# Comms.net
KiCad netlist of a schematic drawn in Altium Designer
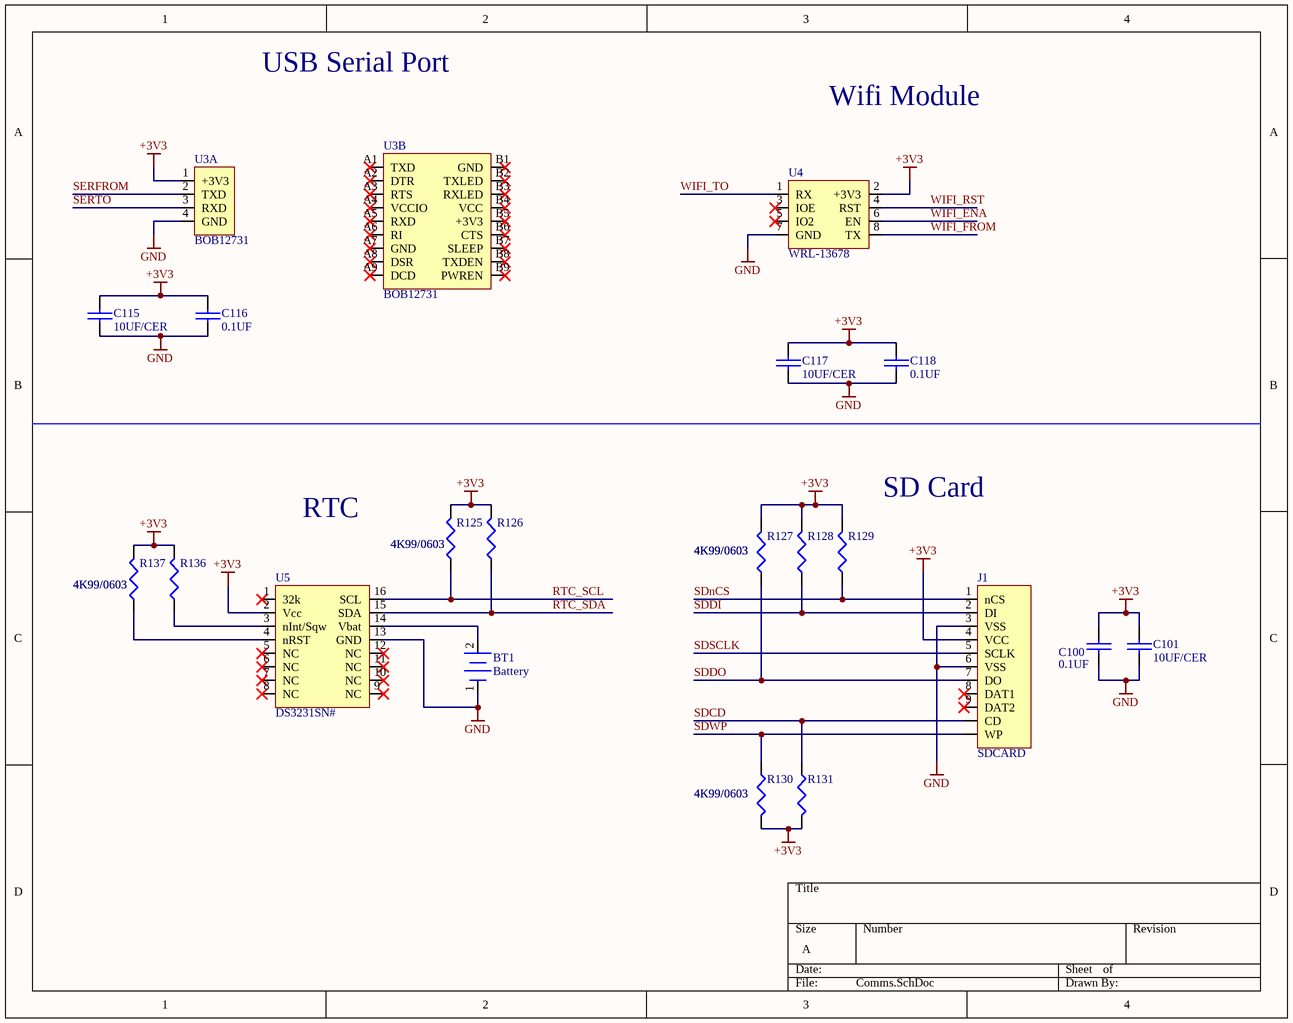
[diagram p0: Comms.SchDoc]

(export (version "E")
  (design (tool "Eeschema 10.0.6"))
  (components
    (comp (ref "BT1")
      (value "Battery")
      (footprint "BC501SM")
      (description "Battery Holder (Open) Coin, 12.0mm 1 Cell SMD (SMT) Tab")
      (fields (field (name "MFG") "MPD"))
      (libsource (lib "C64Interface") (part "BC501SM-TR"))
    )
    (comp (ref "C100")
      (value "0.1UF")
      (footprint "0603")
      (description "CAP .10UF 16V CERAMIC X7R 0603")
      (libsource (lib "*") (part "0.1UF"))
    )
    (comp (ref "C101")
      (value "10UF/CER")
      (footprint "0805")
      (description "10µF ±10% 25V Ceramic Capacitor X7S 0805")
      (libsource (lib "*") (part "10UF/CER"))
    )
    (comp (ref "C115")
      (value "10UF/CER")
      (footprint "0805")
      (description "10µF ±10% 25V Ceramic Capacitor X7S 0805")
      (libsource (lib "C64Interface") (part "10UF/CER"))
    )
    (comp (ref "C116")
      (value "0.1UF")
      (footprint "0603")
      (description "CAP .10UF 16V CERAMIC X7R 0603")
      (fields (field (name "MFG") "Kemet"))
      (libsource (lib "C64Interface") (part "0.1UF"))
    )
    (comp (ref "C117")
      (value "10UF/CER")
      (footprint "0805")
      (description "10µF ±10% 25V Ceramic Capacitor X7S 0805")
      (libsource (lib "C64Interface") (part "10UF/CER"))
    )
    (comp (ref "C118")
      (value "0.1UF")
      (footprint "0603")
      (description "CAP .10UF 16V CERAMIC X7R 0603")
      (fields (field (name "MFG") "Kemet"))
      (libsource (lib "C64Interface") (part "0.1UF"))
    )
    (comp (ref "J1")
      (value "SDCARD")
      (footprint "SDCARD2041021")
      (description "11 (9 + 2) Position Card Connector Secure Digital - SD Surface Mount, Right Angle Gold")
      (fields (field (name "MFG") "TE"))
      (libsource (lib "C64Interface") (part "SDCARD"))
    )
    (comp (ref "R125")
      (value "4K99/0603")
      (footprint "0603")
      (description "RES 4.99K OHM 1/10W 1% 0603 SMD")
      (fields (field (name "MFG") "Dale/Vishay"))
      (libsource (lib "C64Interface") (part "4K99/0603"))
    )
    (comp (ref "R126")
      (value "4K99/0603")
      (footprint "0603")
      (description "RES 4.99K OHM 1/10W 1% 0603 SMD")
      (fields (field (name "MFG") "Dale/Vishay"))
      (libsource (lib "C64Interface") (part "4K99/0603"))
    )
    (comp (ref "R127")
      (value "4K99/0603")
      (footprint "0603")
      (description "RES 4.99K OHM 1/10W 1% 0603 SMD")
      (fields (field (name "MFG") "Dale/Vishay"))
      (libsource (lib "C64Interface") (part "4K99/0603"))
    )
    (comp (ref "R128")
      (value "4K99/0603")
      (footprint "0603")
      (description "RES 4.99K OHM 1/10W 1% 0603 SMD")
      (fields (field (name "MFG") "Dale/Vishay"))
      (libsource (lib "C64Interface") (part "4K99/0603"))
    )
    (comp (ref "R129")
      (value "4K99/0603")
      (footprint "0603")
      (description "RES 4.99K OHM 1/10W 1% 0603 SMD")
      (fields (field (name "MFG") "Dale/Vishay"))
      (libsource (lib "C64Interface") (part "4K99/0603"))
    )
    (comp (ref "R130")
      (value "4K99/0603")
      (footprint "0603")
      (description "RES 4.99K OHM 1/10W 1% 0603 SMD")
      (fields (field (name "MFG") "Dale/Vishay"))
      (libsource (lib "C64Interface") (part "4K99/0603"))
    )
    (comp (ref "R131")
      (value "4K99/0603")
      (footprint "0603")
      (description "RES 4.99K OHM 1/10W 1% 0603 SMD")
      (fields (field (name "MFG") "Dale/Vishay"))
      (libsource (lib "C64Interface") (part "4K99/0603"))
    )
    (comp (ref "R136")
      (value "4K99/0603")
      (footprint "0603")
      (description "RES 4.99K OHM 1/10W 1% 0603 SMD")
      (fields (field (name "MFG") "Dale/Vishay"))
      (libsource (lib "C64Interface") (part "4K99/0603"))
    )
    (comp (ref "R137")
      (value "4K99/0603")
      (footprint "0603")
      (description "RES 4.99K OHM 1/10W 1% 0603 SMD")
      (fields (field (name "MFG") "Dale/Vishay"))
      (libsource (lib "C64Interface") (part "4K99/0603"))
    )
    (comp (ref "U3")
      (value "BOB12731")
      (footprint "BOB12731")
      (description "FT232R USB 2.0 to UART Interface Evaluation Board")
      (fields (field (name "MFG") "SparkFun"))
      (libsource (lib "C64Interface") (part "BOB12731"))
    )
    (comp (ref "U4")
      (value "WRL-13678")
      (footprint "WRL13678")
      (description "WiFi 802.11b/g/n Transceiver Module 2.4GHz ~ 2.48GHz Integrated, Trace Through Hole")
      (fields (field (name "MFG") "SparkFun"))
      (libsource (lib "C64Interface") (part "WRL-13678"))
    )
    (comp (ref "U5")
      (value "DS3231SN#")
      (footprint "SOL16")
      (description "Real Time Clock (RTC) IC Clock/Calendar I²C, 2-Wire Serial 16-SOIC (0.295\", 7.50mm Width)")
      (fields (field (name "MFG") "Maxim"))
      (libsource (lib "C64Interface") (part "DS3231SN#"))
    )
  )
  (nets
    (net (code "1") (name "+3V3") (class "Default")
      (node (ref "C100") (pin "1") (pintype "passive"))
      (node (ref "C101") (pin "2") (pintype "passive"))
      (node (ref "C115") (pin "2") (pintype "passive"))
      (node (ref "C116") (pin "1") (pintype "passive"))
      (node (ref "C117") (pin "2") (pintype "passive"))
      (node (ref "C118") (pin "1") (pintype "passive"))
      (node (ref "J1") (pin "4") (pinfunction "VCC_4") (pintype "passive"))
      (node (ref "R125") (pin "2") (pintype "passive"))
      (node (ref "R126") (pin "2") (pintype "passive"))
      (node (ref "R127") (pin "2") (pintype "passive"))
      (node (ref "R128") (pin "2") (pintype "passive"))
      (node (ref "R129") (pin "2") (pintype "passive"))
      (node (ref "R130") (pin "2") (pintype "passive"))
      (node (ref "R131") (pin "2") (pintype "passive"))
      (node (ref "R136") (pin "2") (pintype "passive"))
      (node (ref "R137") (pin "2") (pintype "passive"))
      (node (ref "U3") (pin "1") (pinfunction "+3V3_1") (pintype "passive"))
      (node (ref "U4") (pin "2") (pinfunction "+3V3_2") (pintype "passive"))
      (node (ref "U5") (pin "2") (pinfunction "Vcc_2") (pintype "passive"))
    )
    (net (code "2") (name "/RTC_SCL") (class "Default")
      (node (ref "R125") (pin "1") (pintype "passive"))
      (node (ref "U5") (pin "16") (pinfunction "SCL_16") (pintype "passive"))
    )
    (net (code "3") (name "/RTC_SDA") (class "Default")
      (node (ref "R126") (pin "1") (pintype "passive"))
      (node (ref "U5") (pin "15") (pinfunction "SDA_15") (pintype "passive"))
    )
    (net (code "4") (name "/SDCD") (class "Default")
      (node (ref "J1") (pin "CD") (pinfunction "CD_CD") (pintype "passive"))
      (node (ref "R131") (pin "1") (pintype "passive"))
    )
    (net (code "5") (name "/SDDI") (class "Default")
      (node (ref "J1") (pin "2") (pinfunction "DI_2") (pintype "passive"))
      (node (ref "R128") (pin "1") (pintype "passive"))
    )
    (net (code "6") (name "/SDDO") (class "Default")
      (node (ref "J1") (pin "7") (pinfunction "DO_7") (pintype "passive"))
      (node (ref "R127") (pin "1") (pintype "passive"))
    )
    (net (code "7") (name "/SDSCLK") (class "Default")
      (node (ref "J1") (pin "5") (pinfunction "SCLK_5") (pintype "passive"))
    )
    (net (code "8") (name "/SDWP") (class "Default")
      (node (ref "J1") (pin "WP") (pinfunction "WP_WP") (pintype "passive"))
      (node (ref "R130") (pin "1") (pintype "passive"))
    )
    (net (code "9") (name "/SDnCS") (class "Default")
      (node (ref "J1") (pin "1") (pinfunction "nCS_1") (pintype "passive"))
      (node (ref "R129") (pin "1") (pintype "passive"))
    )
    (net (code "10") (name "/SERFROM") (class "Default")
      (node (ref "U3") (pin "2") (pinfunction "TXD_2") (pintype "passive"))
    )
    (net (code "11") (name "/SERTO") (class "Default")
      (node (ref "U3") (pin "3") (pinfunction "RXD_3") (pintype "passive"))
    )
    (net (code "12") (name "/WIFI_ENA") (class "Default")
      (node (ref "U4") (pin "6") (pinfunction "EN_6") (pintype "passive"))
    )
    (net (code "13") (name "/WIFI_FROM") (class "Default")
      (node (ref "U4") (pin "8") (pinfunction "TX_8") (pintype "passive"))
    )
    (net (code "14") (name "/WIFI_RST") (class "Default")
      (node (ref "U4") (pin "4") (pinfunction "RST_4") (pintype "passive"))
    )
    (net (code "15") (name "/WIFI_TO") (class "Default")
      (node (ref "U4") (pin "1") (pinfunction "RX_1") (pintype "passive"))
    )
    (net (code "16") (name "GND") (class "Default")
      (node (ref "BT1") (pin "1") (pintype "passive"))
      (node (ref "C100") (pin "2") (pintype "passive"))
      (node (ref "C101") (pin "1") (pintype "passive"))
      (node (ref "C115") (pin "1") (pintype "passive"))
      (node (ref "C116") (pin "2") (pintype "passive"))
      (node (ref "C117") (pin "1") (pintype "passive"))
      (node (ref "C118") (pin "2") (pintype "passive"))
      (node (ref "J1") (pin "3") (pinfunction "VSS_3") (pintype "passive"))
      (node (ref "J1") (pin "6") (pinfunction "VSS_6") (pintype "passive"))
      (node (ref "U3") (pin "4") (pinfunction "GND_4") (pintype "passive"))
      (node (ref "U4") (pin "7") (pinfunction "GND_7") (pintype "passive"))
      (node (ref "U5") (pin "13") (pinfunction "GND_13") (pintype "passive"))
    )
    (net (code "17") (name "Net-(U5-Vbat)") (class "Default")
      (node (ref "BT1") (pin "2") (pintype "passive"))
      (node (ref "U5") (pin "14") (pinfunction "Vbat_14") (pintype "passive"))
    )
    (net (code "18") (name "Net-(U5-nInt{slash}Sqw)") (class "Default")
      (node (ref "R136") (pin "1") (pintype "passive"))
      (node (ref "U5") (pin "3") (pinfunction "nInt/Sqw_3") (pintype "passive"))
    )
    (net (code "19") (name "Net-(U5-nRST)") (class "Default")
      (node (ref "R137") (pin "1") (pintype "passive"))
      (node (ref "U5") (pin "4") (pinfunction "nRST_4") (pintype "passive"))
    )
    (net (code "20") (name "unconnected-(J1-DAT1-Pad8)") (class "Default")
      (node (ref "J1") (pin "8") (pinfunction "DAT1_8") (pintype "passive+no_connect"))
    )
    (net (code "21") (name "unconnected-(J1-DAT2-Pad9)") (class "Default")
      (node (ref "J1") (pin "9") (pinfunction "DAT2_9") (pintype "passive+no_connect"))
    )
    (net (code "22") (name "unconnected-(U3B-+3V3-PadB5)") (class "Default")
      (node (ref "U3") (pin "B5") (pinfunction "+3V3_B5") (pintype "passive+no_connect"))
    )
    (net (code "23") (name "unconnected-(U3B-CTS-PadB6)") (class "Default")
      (node (ref "U3") (pin "B6") (pinfunction "CTS_B6") (pintype "passive+no_connect"))
    )
    (net (code "24") (name "unconnected-(U3B-DCD-PadA9)") (class "Default")
      (node (ref "U3") (pin "A9") (pinfunction "DCD_A9") (pintype "passive+no_connect"))
    )
    (net (code "25") (name "unconnected-(U3B-DSR-PadA8)") (class "Default")
      (node (ref "U3") (pin "A8") (pinfunction "DSR_A8") (pintype "passive+no_connect"))
    )
    (net (code "26") (name "unconnected-(U3B-DTR-PadA2)") (class "Default")
      (node (ref "U3") (pin "A2") (pinfunction "DTR_A2") (pintype "passive+no_connect"))
    )
    (net (code "27") (name "unconnected-(U3B-GND-PadA7)") (class "Default")
      (node (ref "U3") (pin "A7") (pinfunction "GND_A7") (pintype "passive+no_connect"))
    )
    (net (code "28") (name "unconnected-(U3B-GND-PadB1)") (class "Default")
      (node (ref "U3") (pin "B1") (pinfunction "GND_B1") (pintype "passive+no_connect"))
    )
    (net (code "29") (name "unconnected-(U3B-PWREN-PadB9)") (class "Default")
      (node (ref "U3") (pin "B9") (pinfunction "PWREN_B9") (pintype "passive+no_connect"))
    )
    (net (code "30") (name "unconnected-(U3B-RI-PadA6)") (class "Default")
      (node (ref "U3") (pin "A6") (pinfunction "RI_A6") (pintype "passive+no_connect"))
    )
    (net (code "31") (name "unconnected-(U3B-RTS-PadA3)") (class "Default")
      (node (ref "U3") (pin "A3") (pinfunction "RTS_A3") (pintype "passive+no_connect"))
    )
    (net (code "32") (name "unconnected-(U3B-RXD-PadA5)") (class "Default")
      (node (ref "U3") (pin "A5") (pinfunction "RXD_A5") (pintype "passive+no_connect"))
    )
    (net (code "33") (name "unconnected-(U3B-RXLED-PadB3)") (class "Default")
      (node (ref "U3") (pin "B3") (pinfunction "RXLED_B3") (pintype "passive+no_connect"))
    )
    (net (code "34") (name "unconnected-(U3B-SLEEP-PadB7)") (class "Default")
      (node (ref "U3") (pin "B7") (pinfunction "SLEEP_B7") (pintype "passive+no_connect"))
    )
    (net (code "35") (name "unconnected-(U3B-TXD-PadA1)") (class "Default")
      (node (ref "U3") (pin "A1") (pinfunction "TXD_A1") (pintype "passive+no_connect"))
    )
    (net (code "36") (name "unconnected-(U3B-TXDEN-PadB8)") (class "Default")
      (node (ref "U3") (pin "B8") (pinfunction "TXDEN_B8") (pintype "passive+no_connect"))
    )
    (net (code "37") (name "unconnected-(U3B-TXLED-PadB2)") (class "Default")
      (node (ref "U3") (pin "B2") (pinfunction "TXLED_B2") (pintype "passive+no_connect"))
    )
    (net (code "38") (name "unconnected-(U3B-VCC-PadB4)") (class "Default")
      (node (ref "U3") (pin "B4") (pinfunction "VCC_B4") (pintype "passive+no_connect"))
    )
    (net (code "39") (name "unconnected-(U3B-VCCIO-PadA4)") (class "Default")
      (node (ref "U3") (pin "A4") (pinfunction "VCCIO_A4") (pintype "passive+no_connect"))
    )
    (net (code "40") (name "unconnected-(U4-IO2-Pad5)") (class "Default")
      (node (ref "U4") (pin "5") (pinfunction "IO2_5") (pintype "passive+no_connect"))
    )
    (net (code "41") (name "unconnected-(U4-IOE-Pad3)") (class "Default")
      (node (ref "U4") (pin "3") (pinfunction "IOE_3") (pintype "passive+no_connect"))
    )
    (net (code "42") (name "unconnected-(U5-32k-Pad1)") (class "Default")
      (node (ref "U5") (pin "1") (pinfunction "32k_1") (pintype "passive+no_connect"))
    )
    (net (code "43") (name "unconnected-(U5-NC-Pad5)") (class "Default")
      (node (ref "U5") (pin "5") (pinfunction "NC_5") (pintype "passive+no_connect"))
    )
    (net (code "44") (name "unconnected-(U5-NC-Pad6)") (class "Default")
      (node (ref "U5") (pin "6") (pinfunction "NC_6") (pintype "passive+no_connect"))
    )
    (net (code "45") (name "unconnected-(U5-NC-Pad7)") (class "Default")
      (node (ref "U5") (pin "7") (pinfunction "NC_7") (pintype "passive+no_connect"))
    )
    (net (code "46") (name "unconnected-(U5-NC-Pad8)") (class "Default")
      (node (ref "U5") (pin "8") (pinfunction "NC_8") (pintype "passive+no_connect"))
    )
    (net (code "47") (name "unconnected-(U5-NC-Pad9)") (class "Default")
      (node (ref "U5") (pin "9") (pinfunction "NC_9") (pintype "passive+no_connect"))
    )
    (net (code "48") (name "unconnected-(U5-NC-Pad10)") (class "Default")
      (node (ref "U5") (pin "10") (pinfunction "NC_10") (pintype "passive+no_connect"))
    )
    (net (code "49") (name "unconnected-(U5-NC-Pad11)") (class "Default")
      (node (ref "U5") (pin "11") (pinfunction "NC_11") (pintype "passive+no_connect"))
    )
    (net (code "50") (name "unconnected-(U5-NC-Pad12)") (class "Default")
      (node (ref "U5") (pin "12") (pinfunction "NC_12") (pintype "passive+no_connect"))
    )
  )
)
